# Aixcel_Tiny_STLink_Board_Page1.net
KiCad netlist of a schematic drawn in Altium Designer
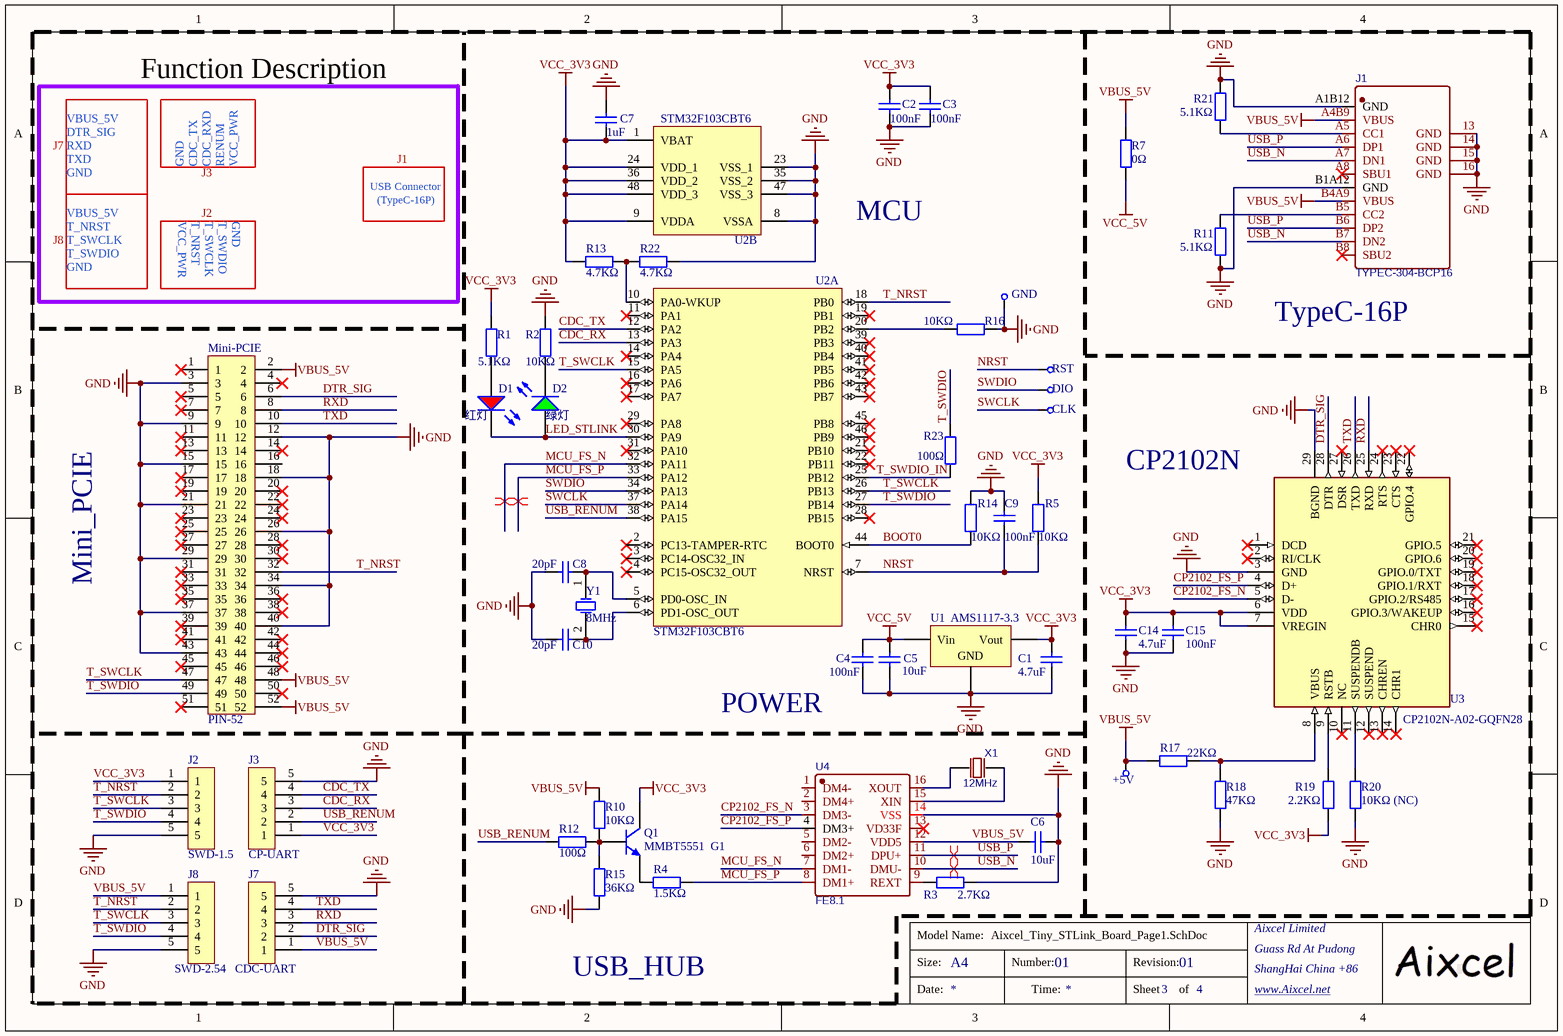
[diagram p0: Aixcel_Tiny_STLink_Board_Page1.SchDoc]

(export (version "E")
  (design (tool "Eeschema 10.0.6"))
  (components
    (comp (ref "+5V")
      (value "CHECK")
      (footprint "CHECK-D")
      (description "测试点")
      (libsource (lib "fszhang") (part "CHECK"))
    )
    (comp (ref "C1")
      (value "4.7uF")
      (footprint "0603_C")
      (description "贴片电容")
      (libsource (lib "Miscellaneous Devices LC") (part "0603 4.7uF (475) 10% 16V"))
    )
    (comp (ref "C2")
      (value "100nF")
      (footprint "0603_C")
      (description "贴片电容")
      (libsource (lib "Miscellaneous Devices LC") (part "0603 100nF (104) 10% 50V"))
    )
    (comp (ref "C3")
      (value "100nF")
      (footprint "0603_C")
      (description "贴片电容")
      (libsource (lib "Miscellaneous Devices LC") (part "0603 100nF (104) 10% 50V"))
    )
    (comp (ref "C4")
      (value "100nF")
      (footprint "0603_C")
      (description "贴片电容")
      (libsource (lib "Miscellaneous Devices LC") (part "0603 100nF (104) 10% 50V"))
    )
    (comp (ref "C5")
      (value "10uF")
      (footprint "0603_C")
      (description "贴片电容")
      (libsource (lib "Miscellaneous Devices LC") (part "0603 10uF (106) 10% 10V"))
    )
    (comp (ref "C6")
      (value "10uF")
      (footprint "0603_C")
      (description "贴片电容")
      (libsource (lib "Miscellaneous Devices LC") (part "0603 10uF (106) 10% 10V"))
    )
    (comp (ref "C7")
      (value "1uF")
      (footprint "0603_C")
      (description "贴片电容")
      (libsource (lib "Miscellaneous Devices LC") (part "0603 1uF (105) 10% 50V"))
    )
    (comp (ref "C8")
      (value "20pF")
      (footprint "0603_C")
      (description "贴片电容")
      (libsource (lib "Miscellaneous Devices LC") (part "0603 20pF (200) 5% 50V"))
    )
    (comp (ref "C9")
      (value "100nF")
      (footprint "0603_C")
      (description "贴片电容")
      (libsource (lib "Miscellaneous Devices LC") (part "0603 100nF (104) 10% 50V"))
    )
    (comp (ref "C10")
      (value "20pF")
      (footprint "0603_C")
      (description "贴片电容")
      (libsource (lib "Miscellaneous Devices LC") (part "0603 20pF (200) 5% 50V"))
    )
    (comp (ref "C14")
      (value "4.7uF")
      (footprint "0603_C")
      (description "贴片电容")
      (libsource (lib "Miscellaneous Devices LC") (part "0603 4.7uF (475) 10% 16V"))
    )
    (comp (ref "C15")
      (value "100nF")
      (footprint "0603_C")
      (description "贴片电容")
      (libsource (lib "Miscellaneous Devices LC") (part "0603 100nF (104) 10% 50V"))
    )
    (comp (ref "CLK")
      (value "CHECK")
      (footprint "CHECK-D")
      (description "测试点")
      (libsource (lib "fszhang") (part "CHECK"))
    )
    (comp (ref "D1")
      (value "红灯")
      (footprint "0603_LED_S1")
      (description "发光二极管")
      (libsource (lib "Miscellaneous Devices LC") (part "0603 红灯"))
    )
    (comp (ref "D2")
      (value "绿灯")
      (footprint "0603_LED_S1")
      (description "发光二极管")
      (libsource (lib "Miscellaneous Devices LC") (part "0603 绿灯"))
    )
    (comp (ref "DIO")
      (value "CHECK")
      (footprint "CHECK-D")
      (description "测试点")
      (libsource (lib "fszhang") (part "CHECK"))
    )
    (comp (ref "GND")
      (value "CHECK")
      (footprint "CHECK-D")
      (description "测试点")
      (libsource (lib "fszhang") (part "CHECK"))
    )
    (comp (ref "J1")
      (value "TYPEC-304-BCP16")
      (footprint "TypeC-16Pin")
      (fields (field (name "BOM_SUPPLIER PART") "C720629") (field (name "CONTRIBUTOR") "LCSC"))
      (libsource (lib "其他") (part "TYPEC-304-BCP16"))
    )
    (comp (ref "J2") (value "SWD-1.5") (footprint "ZH1.5-LI-5P") (libsource (lib "接插件") (part "SIP-5")))
    (comp (ref "J3") (value "CP-UART") (footprint "ZH1.5-LI-5P") (libsource (lib "") (part "SIP-5_1")))
    (comp (ref "J7") (value "CDC-UART") (footprint "2.54XH接插件5P") (libsource (lib "") (part "SIP-5_1")))
    (comp (ref "J8") (value "SWD-2.54") (footprint "2.54XH接插件5P") (libsource (lib "接插件") (part "SIP-5")))
    (comp (ref "Mini-PCIE")
      (value "PIN-52")
      (footprint "PCBComponent_1")
      (libsource (lib "接插件") (part "PIN-52"))
    )
    (comp (ref "Q1")
      (value "MMBT5551  G1")
      (footprint "SOT-23(SOT-23-3)")
      (description "三极管")
      (libsource (lib "Miscellaneous Devices LC") (part "SOT-23 MMBT5551  G1"))
    )
    (comp (ref "R1")
      (value "5.1KΩ")
      (footprint "0603_R")
      (description "贴片电阻")
      (libsource (lib "") (part "0603 5.1KΩ (5101) 1%_1"))
    )
    (comp (ref "R2")
      (value "10KΩ")
      (footprint "0603_R")
      (description "贴片电阻")
      (libsource (lib "") (part "0603 10KΩ (1002) 1%_1"))
    )
    (comp (ref "R3")
      (value "2.7KΩ")
      (footprint "0603_R")
      (description "贴片电阻")
      (libsource (lib "Miscellaneous Devices LC") (part "0603 2.7KΩ (2701) 1%"))
    )
    (comp (ref "R4")
      (value "1.5KΩ")
      (footprint "0603_R")
      (description "贴片电阻")
      (libsource (lib "Miscellaneous Devices LC") (part "0603 1.5KΩ (1501) 1%"))
    )
    (comp (ref "R5")
      (value "10KΩ")
      (footprint "0603_R")
      (description "贴片电阻")
      (libsource (lib "") (part "0603 10KΩ (1002) 1%_1"))
    )
    (comp (ref "R7")
      (value "0Ω")
      (footprint "0805_R")
      (description "贴片电阻")
      (libsource (lib "Miscellaneous Devices LC") (part "0805 0Ω (0R0) 1%"))
    )
    (comp (ref "R10")
      (value "10KΩ")
      (footprint "0603_R")
      (description "贴片电阻")
      (libsource (lib "") (part "0603 10KΩ (1002) 1%_1"))
    )
    (comp (ref "R11")
      (value "5.1KΩ")
      (footprint "0603_R")
      (description "贴片电阻")
      (libsource (lib "Miscellaneous Devices LC") (part "0603 5.1KΩ (5101) 1%"))
    )
    (comp (ref "R12")
      (value "100Ω")
      (footprint "0603_R")
      (description "贴片电阻")
      (libsource (lib "Miscellaneous Devices LC") (part "0603 100Ω (1000) 1%"))
    )
    (comp (ref "R13")
      (value "4.7KΩ")
      (footprint "0603_R")
      (description "贴片电阻")
      (libsource (lib "Miscellaneous Devices LC") (part "0603 4.7KΩ (4701) 1%"))
    )
    (comp (ref "R14")
      (value "10KΩ")
      (footprint "0603_R")
      (description "贴片电阻")
      (libsource (lib "Miscellaneous Devices LC") (part "0603 10KΩ (1002) 1%"))
    )
    (comp (ref "R15")
      (value "36KΩ")
      (footprint "0603_R")
      (description "贴片电阻")
      (libsource (lib "Miscellaneous Devices LC") (part "0603 36KΩ (3602) 1%"))
    )
    (comp (ref "R16")
      (value "10KΩ")
      (footprint "0603_R")
      (description "贴片电阻")
      (libsource (lib "") (part "0603 10KΩ (1002) 1%_2"))
    )
    (comp (ref "R17")
      (value "22KΩ")
      (footprint "0603_R")
      (description "贴片电阻")
      (libsource (lib "Miscellaneous Devices LC") (part "0603 22KΩ (2202) 1%"))
    )
    (comp (ref "R18")
      (value "47KΩ")
      (footprint "0603_R")
      (description "贴片电阻")
      (libsource (lib "Miscellaneous Devices LC") (part "0603 47KΩ (4702) 1%"))
    )
    (comp (ref "R19")
      (value "2.2KΩ")
      (footprint "0603_R")
      (description "贴片电阻")
      (libsource (lib "Miscellaneous Devices LC") (part "0603 2.2KΩ (2201) 1%"))
    )
    (comp (ref "R20")
      (value "10KΩ (NC)")
      (footprint "0603_R")
      (description "贴片电阻")
      (libsource (lib "Miscellaneous Devices LC") (part "0603 10KΩ (1002) 1%"))
    )
    (comp (ref "R21")
      (value "5.1KΩ")
      (footprint "0603_R")
      (description "贴片电阻")
      (libsource (lib "Miscellaneous Devices LC") (part "0603 5.1KΩ (5101) 1%"))
    )
    (comp (ref "R22")
      (value "4.7KΩ")
      (footprint "0603_R")
      (description "贴片电阻")
      (libsource (lib "Miscellaneous Devices LC") (part "0603 4.7KΩ (4701) 1%"))
    )
    (comp (ref "R23")
      (value "100Ω")
      (footprint "0603_R")
      (description "贴片电阻")
      (libsource (lib "") (part "0603 100Ω (1000) 1%_1"))
    )
    (comp (ref "RST")
      (value "CHECK")
      (footprint "CHECK-D")
      (description "测试点")
      (libsource (lib "fszhang") (part "CHECK"))
    )
    (comp (ref "U1")
      (value "AMS1117-3.3")
      (footprint "SOT-223")
      (description "低压差线性稳压(LDO)")
      (libsource (lib "Miscellaneous Devices LC") (part "SOT-223 AMS1117-3.3"))
    )
    (comp (ref "U2")
      (value "STM32F103CBT6")
      (footprint "STM-LQFP48_L")
      (libsource (lib "STMicroelectronics STM32 F1") (part "STM32F103CBT6"))
    )
    (comp (ref "U3")
      (value "CP2102N-A02-GQFN28")
      (footprint "SamacSys:QFN50P500X500X80-29N-D")
      (description "Integrated Circuit")
      (fields (field (name "MOUSER2 PART NUMBER") "634-CP2102NA02GQFN28"))
      (libsource (lib "*") (part "CP2102N-A02-GQFN28"))
    )
    (comp (ref "U4")
      (value "FE8.1")
      (footprint "SSOP-16_L4.9-W3.9-P0.64-LS6.0-BL")
      (fields (field (name "CONTRIBUTOR") "私有工程"))
      (libsource (lib "FE8.1") (part "FE8.1"))
    )
    (comp (ref "X1")
      (value "12MHz")
      (footprint "12MHz")
      (fields
        (field (name "BOM_SUPPLIER PART") "C33728")
        (field (name "BOM_MANUFACTURER PART") "X503212MSD2GC")
      )
      (libsource (lib "其他") (part "12MHz"))
    )
    (comp (ref "Y1")
      (value "8MHz")
      (footprint "SMD-5032_2P")
      (description "贴片晶振")
      (libsource (lib "Miscellaneous Devices LC") (part "SMD-5032_2P 8MHz 20ppm 20pF"))
    )
  )
  (nets
    (net (code "1") (name "/BOOT0") (class "Default")
      (node (ref "R14") (pin "2") (pinfunction "2_2") (pintype "passive"))
      (node (ref "U2") (pin "44") (pinfunction "BOOT0_44") (pintype "input"))
    )
    (net (code "2") (name "/CDC_RX") (class "Default")
      (node (ref "J3") (pin "3") (pinfunction "3_3") (pintype "passive"))
      (node (ref "U2") (pin "13") (pinfunction "PA3_13") (pintype "bidirectional"))
    )
    (net (code "3") (name "/CDC_TX") (class "Default")
      (node (ref "J3") (pin "4") (pinfunction "4_4") (pintype "passive"))
      (node (ref "U2") (pin "12") (pinfunction "PA2_12") (pintype "bidirectional"))
    )
    (net (code "4") (name "/CP2102_FS_N") (class "Default")
      (node (ref "U3") (pin "5") (pinfunction "D-_5") (pintype "bidirectional"))
      (node (ref "U4") (pin "3") (pinfunction "DM3-_3") (pintype "passive"))
    )
    (net (code "5") (name "/CP2102_FS_P") (class "Default")
      (node (ref "U3") (pin "4") (pinfunction "D+_4") (pintype "bidirectional"))
      (node (ref "U4") (pin "4") (pinfunction "DM3+_4") (pintype "passive"))
    )
    (net (code "6") (name "/DTR_SIG") (class "Default")
      (node (ref "J7") (pin "2") (pinfunction "2_2") (pintype "passive"))
      (node (ref "Mini-PCIE") (pin "6") (pinfunction "6_6") (pintype "passive"))
      (node (ref "U3") (pin "28") (pinfunction "DTR_28") (pintype "output"))
    )
    (net (code "7") (name "/LED_STLINK") (class "Default")
      (node (ref "D1") (pin "K") (pinfunction "K_K") (pintype "passive"))
      (node (ref "D2") (pin "A") (pinfunction "A_A") (pintype "passive"))
      (node (ref "U2") (pin "30") (pinfunction "PA9_30") (pintype "bidirectional"))
    )
    (net (code "8") (name "/MCU_FS_N") (class "Default")
      (node (ref "U2") (pin "32") (pinfunction "PA11_32") (pintype "bidirectional"))
      (node (ref "U4") (pin "7") (pinfunction "DM1-_7") (pintype "passive"))
    )
    (net (code "9") (name "/MCU_FS_P") (class "Default")
      (node (ref "R4") (pin "1") (pinfunction "1_1") (pintype "passive"))
      (node (ref "U2") (pin "33") (pinfunction "PA12_33") (pintype "bidirectional"))
      (node (ref "U4") (pin "8") (pinfunction "DM1+_8") (pintype "passive"))
    )
    (net (code "10") (name "/NRST") (class "Default")
      (node (ref "C9") (pin "1") (pinfunction "1_1") (pintype "passive"))
      (node (ref "R5") (pin "1") (pinfunction "1_1") (pintype "passive"))
      (node (ref "RST") (pin "1") (pinfunction "1_1") (pintype "passive"))
      (node (ref "U2") (pin "7") (pinfunction "NRST_7") (pintype "bidirectional"))
    )
    (net (code "11") (name "/RXD") (class "Default")
      (node (ref "J7") (pin "3") (pinfunction "3_3") (pintype "passive"))
      (node (ref "Mini-PCIE") (pin "8") (pinfunction "8_8") (pintype "passive"))
      (node (ref "U3") (pin "25") (pinfunction "RXD_25") (pintype "input"))
    )
    (net (code "12") (name "/SWCLK") (class "Default")
      (node (ref "CLK") (pin "1") (pinfunction "1_1") (pintype "passive"))
      (node (ref "U2") (pin "37") (pinfunction "PA14_37") (pintype "bidirectional"))
    )
    (net (code "13") (name "/SWDIO") (class "Default")
      (node (ref "DIO") (pin "1") (pinfunction "1_1") (pintype "passive"))
      (node (ref "U2") (pin "34") (pinfunction "PA13_34") (pintype "bidirectional"))
    )
    (net (code "14") (name "/TXD") (class "Default")
      (node (ref "J7") (pin "4") (pinfunction "4_4") (pintype "passive"))
      (node (ref "Mini-PCIE") (pin "10") (pinfunction "10_10") (pintype "passive"))
      (node (ref "U3") (pin "26") (pinfunction "TXD_26") (pintype "output"))
    )
    (net (code "15") (name "/T_NRST") (class "Default")
      (node (ref "J2") (pin "2") (pinfunction "2_2") (pintype "passive"))
      (node (ref "J8") (pin "2") (pinfunction "2_2") (pintype "passive"))
      (node (ref "Mini-PCIE") (pin "32") (pinfunction "32_32") (pintype "passive"))
      (node (ref "U2") (pin "18") (pinfunction "PB0_18") (pintype "bidirectional"))
    )
    (net (code "16") (name "/T_SWCLK") (class "Default")
      (node (ref "J2") (pin "3") (pinfunction "3_3") (pintype "passive"))
      (node (ref "J8") (pin "3") (pinfunction "3_3") (pintype "passive"))
      (node (ref "Mini-PCIE") (pin "47") (pinfunction "47_47") (pintype "passive"))
      (node (ref "U2") (pin "15") (pinfunction "PA5_15") (pintype "bidirectional"))
      (node (ref "U2") (pin "26") (pinfunction "PB13_26") (pintype "bidirectional"))
    )
    (net (code "17") (name "/T_SWDIO") (class "Default")
      (node (ref "J2") (pin "4") (pinfunction "4_4") (pintype "passive"))
      (node (ref "J8") (pin "4") (pinfunction "4_4") (pintype "passive"))
      (node (ref "Mini-PCIE") (pin "49") (pinfunction "49_49") (pintype "passive"))
      (node (ref "R23") (pin "2") (pinfunction "2_2") (pintype "passive"))
      (node (ref "U2") (pin "27") (pinfunction "PB14_27") (pintype "bidirectional"))
    )
    (net (code "18") (name "/T_SWDIO_IN") (class "Default")
      (node (ref "R23") (pin "1") (pinfunction "1_1") (pintype "passive"))
      (node (ref "U2") (pin "25") (pinfunction "PB12_25") (pintype "bidirectional"))
    )
    (net (code "19") (name "/USB_N") (class "Default")
      (node (ref "J1") (pin "A7") (pinfunction "DN1_A7") (pintype "passive"))
      (node (ref "J1") (pin "B7") (pinfunction "DN2_B7") (pintype "passive"))
      (node (ref "U4") (pin "10") (pinfunction "DMU-_10") (pintype "passive"))
    )
    (net (code "20") (name "/USB_P") (class "Default")
      (node (ref "J1") (pin "A6") (pinfunction "DP1_A6") (pintype "passive"))
      (node (ref "J1") (pin "B6") (pinfunction "DP2_B6") (pintype "passive"))
      (node (ref "U4") (pin "11") (pinfunction "DPU+_11") (pintype "passive"))
    )
    (net (code "21") (name "/USB_RENUM") (class "Default")
      (node (ref "J3") (pin "2") (pinfunction "2_2") (pintype "passive"))
      (node (ref "R12") (pin "1") (pinfunction "1_1") (pintype "passive"))
      (node (ref "U2") (pin "38") (pinfunction "PA15_38") (pintype "bidirectional"))
    )
    (net (code "22") (name "GND") (class "Default")
      (node (ref "C1") (pin "1") (pinfunction "1_1") (pintype "passive"))
      (node (ref "C10") (pin "1") (pinfunction "1_1") (pintype "passive"))
      (node (ref "C14") (pin "1") (pinfunction "1_1") (pintype "passive"))
      (node (ref "C15") (pin "1") (pinfunction "1_1") (pintype "passive"))
      (node (ref "C2") (pin "2") (pinfunction "2_2") (pintype "passive"))
      (node (ref "C3") (pin "2") (pinfunction "2_2") (pintype "passive"))
      (node (ref "C4") (pin "1") (pinfunction "1_1") (pintype "passive"))
      (node (ref "C5") (pin "1") (pinfunction "1_1") (pintype "passive"))
      (node (ref "C6") (pin "1") (pinfunction "1_1") (pintype "passive"))
      (node (ref "C7") (pin "2") (pinfunction "2_2") (pintype "passive"))
      (node (ref "C8") (pin "1") (pinfunction "1_1") (pintype "passive"))
      (node (ref "C9") (pin "2") (pinfunction "2_2") (pintype "passive"))
      (node (ref "GND") (pin "1") (pinfunction "1_1") (pintype "passive"))
      (node (ref "J1") (pin "13") (pinfunction "GND_13") (pintype "passive"))
      (node (ref "J1") (pin "14") (pinfunction "GND_14") (pintype "passive"))
      (node (ref "J1") (pin "15") (pinfunction "GND_15") (pintype "passive"))
      (node (ref "J1") (pin "16") (pinfunction "GND_16") (pintype "passive"))
      (node (ref "J1") (pin "A1B12") (pinfunction "GND_A1B12") (pintype "passive"))
      (node (ref "J1") (pin "B1A12") (pinfunction "GND_B1A12") (pintype "passive"))
      (node (ref "J2") (pin "5") (pinfunction "5_5") (pintype "passive"))
      (node (ref "J3") (pin "5") (pinfunction "5_5") (pintype "passive"))
      (node (ref "J7") (pin "5") (pinfunction "5_5") (pintype "passive"))
      (node (ref "J8") (pin "5") (pinfunction "5_5") (pintype "passive"))
      (node (ref "Mini-PCIE") (pin "12") (pinfunction "12_12") (pintype "passive"))
      (node (ref "Mini-PCIE") (pin "15") (pinfunction "15_15") (pintype "passive"))
      (node (ref "Mini-PCIE") (pin "18") (pinfunction "18_18") (pintype "passive"))
      (node (ref "Mini-PCIE") (pin "21") (pinfunction "21_21") (pintype "passive"))
      (node (ref "Mini-PCIE") (pin "26") (pinfunction "26_26") (pintype "passive"))
      (node (ref "Mini-PCIE") (pin "29") (pinfunction "29_29") (pintype "passive"))
      (node (ref "Mini-PCIE") (pin "3") (pinfunction "3_3") (pintype "passive"))
      (node (ref "Mini-PCIE") (pin "34") (pinfunction "34_34") (pintype "passive"))
      (node (ref "Mini-PCIE") (pin "37") (pinfunction "37_37") (pintype "passive"))
      (node (ref "Mini-PCIE") (pin "40") (pinfunction "40_40") (pintype "passive"))
      (node (ref "Mini-PCIE") (pin "43") (pinfunction "43_43") (pintype "passive"))
      (node (ref "Mini-PCIE") (pin "9") (pinfunction "9_9") (pintype "passive"))
      (node (ref "R11") (pin "1") (pinfunction "1_1") (pintype "passive"))
      (node (ref "R14") (pin "1") (pinfunction "1_1") (pintype "passive"))
      (node (ref "R15") (pin "1") (pinfunction "1_1") (pintype "passive"))
      (node (ref "R16") (pin "1") (pinfunction "1_1") (pintype "passive"))
      (node (ref "R18") (pin "1") (pinfunction "1_1") (pintype "passive"))
      (node (ref "R2") (pin "2") (pinfunction "2_2") (pintype "passive"))
      (node (ref "R20") (pin "2") (pinfunction "2_2") (pintype "passive"))
      (node (ref "R21") (pin "2") (pinfunction "2_2") (pintype "passive"))
      (node (ref "R22") (pin "1") (pinfunction "1_1") (pintype "passive"))
      (node (ref "R3") (pin "2") (pinfunction "2_2") (pintype "passive"))
      (node (ref "U1") (pin "1") (pinfunction "GND_1") (pintype "passive"))
      (node (ref "U2") (pin "23") (pinfunction "VSS_1_23") (pintype "power_in"))
      (node (ref "U2") (pin "35") (pinfunction "VSS_2_35") (pintype "power_in"))
      (node (ref "U2") (pin "47") (pinfunction "VSS_3_47") (pintype "power_in"))
      (node (ref "U2") (pin "8") (pinfunction "VSSA_8") (pintype "power_in"))
      (node (ref "U3") (pin "29") (pinfunction "BGND_29") (pintype "power_in"))
      (node (ref "U3") (pin "3") (pinfunction "GND_3") (pintype "power_in"))
      (node (ref "U4") (pin "14") (pinfunction "VSS_14") (pintype "passive"))
    )
    (net (code "23") (name "Net-(D1-PadA)") (class "Default")
      (node (ref "D1") (pin "A") (pinfunction "A_A") (pintype "passive"))
      (node (ref "R1") (pin "2") (pinfunction "2_2") (pintype "passive"))
    )
    (net (code "24") (name "Net-(D2-PadK)") (class "Default")
      (node (ref "D2") (pin "K") (pinfunction "K_K") (pintype "passive"))
      (node (ref "R2") (pin "1") (pinfunction "1_1") (pintype "passive"))
    )
    (net (code "25") (name "Net-(J1-CC1)") (class "Default")
      (node (ref "J1") (pin "A5") (pinfunction "CC1_A5") (pintype "passive"))
      (node (ref "R21") (pin "1") (pinfunction "1_1") (pintype "passive"))
    )
    (net (code "26") (name "Net-(J1-CC2)") (class "Default")
      (node (ref "J1") (pin "B5") (pinfunction "CC2_B5") (pintype "passive"))
      (node (ref "R11") (pin "2") (pinfunction "2_2") (pintype "passive"))
    )
    (net (code "27") (name "Net-(Q1-B)") (class "Default")
      (node (ref "Q1") (pin "1") (pinfunction "B_1") (pintype "passive"))
      (node (ref "R10") (pin "1") (pinfunction "1_1") (pintype "passive"))
      (node (ref "R12") (pin "2") (pinfunction "2_2") (pintype "passive"))
      (node (ref "R15") (pin "2") (pinfunction "2_2") (pintype "passive"))
    )
    (net (code "28") (name "Net-(Q1-E)") (class "Default")
      (node (ref "Q1") (pin "2") (pinfunction "E_2") (pintype "passive"))
      (node (ref "R4") (pin "2") (pinfunction "2_2") (pintype "passive"))
    )
    (net (code "29") (name "Net-(U2A-PA0-WKUP)") (class "Default")
      (node (ref "R13") (pin "1") (pinfunction "1_1") (pintype "passive"))
      (node (ref "R22") (pin "2") (pinfunction "2_2") (pintype "passive"))
      (node (ref "U2") (pin "10") (pinfunction "PA0-WKUP_10") (pintype "bidirectional"))
    )
    (net (code "30") (name "Net-(U2A-PB2)") (class "Default")
      (node (ref "R16") (pin "2") (pinfunction "2_2") (pintype "passive"))
      (node (ref "U2") (pin "20") (pinfunction "PB2_20") (pintype "bidirectional"))
    )
    (net (code "31") (name "Net-(U2A-PD0-OSC_IN)") (class "Default")
      (node (ref "C8") (pin "2") (pinfunction "2_2") (pintype "passive"))
      (node (ref "U2") (pin "5") (pinfunction "PD0-OSC_IN_5") (pintype "bidirectional"))
      (node (ref "Y1") (pin "1") (pinfunction "OSC1_1") (pintype "passive"))
    )
    (net (code "32") (name "Net-(U2A-PD1-OSC_OUT)") (class "Default")
      (node (ref "C10") (pin "2") (pinfunction "2_2") (pintype "passive"))
      (node (ref "U2") (pin "6") (pinfunction "PD1-OSC_OUT_6") (pintype "bidirectional"))
      (node (ref "Y1") (pin "2") (pinfunction "OSC2_2") (pintype "passive"))
    )
    (net (code "33") (name "Net-(U3-RSTB)") (class "Default")
      (node (ref "R19") (pin "2") (pinfunction "2_2") (pintype "passive"))
      (node (ref "U3") (pin "9") (pinfunction "RSTB_9") (pintype "input"))
    )
    (net (code "34") (name "Net-(U3-SUSPENDB)") (class "Default")
      (node (ref "R20") (pin "1") (pinfunction "1_1") (pintype "passive"))
      (node (ref "U3") (pin "11") (pinfunction "SUSPENDB_11") (pintype "output"))
    )
    (net (code "35") (name "Net-(U3-VBUS)") (class "Default")
      (node (ref "R17") (pin "2") (pinfunction "2_2") (pintype "passive"))
      (node (ref "R18") (pin "2") (pinfunction "2_2") (pintype "passive"))
      (node (ref "U3") (pin "8") (pinfunction "VBUS_8") (pintype "input"))
    )
    (net (code "36") (name "Net-(U4-REXT)") (class "Default")
      (node (ref "R3") (pin "1") (pinfunction "1_1") (pintype "passive"))
      (node (ref "U4") (pin "9") (pinfunction "REXT_9") (pintype "passive"))
    )
    (net (code "37") (name "Net-(U4-XIN)") (class "Default")
      (node (ref "U4") (pin "15") (pinfunction "XIN_15") (pintype "passive"))
      (node (ref "X1") (pin "2") (pinfunction "OSC2_2") (pintype "passive"))
    )
    (net (code "38") (name "Net-(U4-XOUT)") (class "Default")
      (node (ref "U4") (pin "16") (pinfunction "XOUT_16") (pintype "passive"))
      (node (ref "X1") (pin "1") (pinfunction "OSC1_1") (pintype "passive"))
    )
    (net (code "39") (name "VBUS_5V") (class "Default")
      (node (ref "+5V") (pin "1") (pinfunction "1_1") (pintype "passive"))
      (node (ref "C6") (pin "2") (pinfunction "2_2") (pintype "passive"))
      (node (ref "J1") (pin "A4B9") (pinfunction "VBUS_A4B9") (pintype "passive"))
      (node (ref "J1") (pin "B4A9") (pinfunction "VBUS_B4A9") (pintype "passive"))
      (node (ref "J7") (pin "1") (pinfunction "1_1") (pintype "passive"))
      (node (ref "J8") (pin "1") (pinfunction "1_1") (pintype "passive"))
      (node (ref "Mini-PCIE") (pin "2") (pinfunction "2_2") (pintype "passive"))
      (node (ref "Mini-PCIE") (pin "48") (pinfunction "48_48") (pintype "passive"))
      (node (ref "Mini-PCIE") (pin "52") (pinfunction "52_52") (pintype "passive"))
      (node (ref "R10") (pin "2") (pinfunction "2_2") (pintype "passive"))
      (node (ref "R17") (pin "1") (pinfunction "1_1") (pintype "passive"))
      (node (ref "R7") (pin "2") (pinfunction "2_2") (pintype "passive"))
      (node (ref "U4") (pin "12") (pinfunction "VDD5_12") (pintype "passive"))
    )
    (net (code "40") (name "VCC_3V3") (class "Default")
      (node (ref "C1") (pin "2") (pinfunction "2_2") (pintype "passive"))
      (node (ref "C14") (pin "2") (pinfunction "2_2") (pintype "passive"))
      (node (ref "C15") (pin "2") (pinfunction "2_2") (pintype "passive"))
      (node (ref "C2") (pin "1") (pinfunction "1_1") (pintype "passive"))
      (node (ref "C3") (pin "1") (pinfunction "1_1") (pintype "passive"))
      (node (ref "C7") (pin "1") (pinfunction "1_1") (pintype "passive"))
      (node (ref "J2") (pin "1") (pinfunction "1_1") (pintype "passive"))
      (node (ref "J3") (pin "1") (pinfunction "1_1") (pintype "passive"))
      (node (ref "Q1") (pin "3") (pinfunction "C_3") (pintype "passive"))
      (node (ref "R1") (pin "1") (pinfunction "1_1") (pintype "passive"))
      (node (ref "R13") (pin "2") (pinfunction "2_2") (pintype "passive"))
      (node (ref "R19") (pin "1") (pinfunction "1_1") (pintype "passive"))
      (node (ref "R5") (pin "2") (pinfunction "2_2") (pintype "passive"))
      (node (ref "U1") (pin "2") (pinfunction "Vout_2") (pintype "passive"))
      (node (ref "U2") (pin "1") (pinfunction "VBAT_1") (pintype "power_in"))
      (node (ref "U2") (pin "24") (pinfunction "VDD_1_24") (pintype "power_in"))
      (node (ref "U2") (pin "36") (pinfunction "VDD_2_36") (pintype "power_in"))
      (node (ref "U2") (pin "48") (pinfunction "VDD_3_48") (pintype "power_in"))
      (node (ref "U2") (pin "9") (pinfunction "VDDA_9") (pintype "power_in"))
      (node (ref "U3") (pin "6") (pinfunction "VDD_6") (pintype "power_in"))
      (node (ref "U3") (pin "7") (pinfunction "VREGIN_7") (pintype "power_in"))
    )
    (net (code "41") (name "VCC_5V") (class "Default")
      (node (ref "C4") (pin "2") (pinfunction "2_2") (pintype "passive"))
      (node (ref "C5") (pin "2") (pinfunction "2_2") (pintype "passive"))
      (node (ref "R7") (pin "1") (pinfunction "1_1") (pintype "passive"))
      (node (ref "U1") (pin "3") (pinfunction "Vin_3") (pintype "passive"))
    )
    (net (code "42") (name "unconnected-(J1-SBU1-PadA8)") (class "Default")
      (node (ref "J1") (pin "A8") (pinfunction "SBU1_A8") (pintype "passive+no_connect"))
    )
    (net (code "43") (name "unconnected-(J1-SBU2-PadB8)") (class "Default")
      (node (ref "J1") (pin "B8") (pinfunction "SBU2_B8") (pintype "passive+no_connect"))
    )
    (net (code "44") (name "unconnected-(Mini-PCIE-Pad1)") (class "Default")
      (node (ref "Mini-PCIE") (pin "1") (pinfunction "1_1") (pintype "passive+no_connect"))
    )
    (net (code "45") (name "unconnected-(Mini-PCIE-Pad4)") (class "Default")
      (node (ref "Mini-PCIE") (pin "4") (pinfunction "4_4") (pintype "passive+no_connect"))
    )
    (net (code "46") (name "unconnected-(Mini-PCIE-Pad5)") (class "Default")
      (node (ref "Mini-PCIE") (pin "5") (pinfunction "5_5") (pintype "passive+no_connect"))
    )
    (net (code "47") (name "unconnected-(Mini-PCIE-Pad7)") (class "Default")
      (node (ref "Mini-PCIE") (pin "7") (pinfunction "7_7") (pintype "passive+no_connect"))
    )
    (net (code "48") (name "unconnected-(Mini-PCIE-Pad11)") (class "Default")
      (node (ref "Mini-PCIE") (pin "11") (pinfunction "11_11") (pintype "passive+no_connect"))
    )
    (net (code "49") (name "unconnected-(Mini-PCIE-Pad13)") (class "Default")
      (node (ref "Mini-PCIE") (pin "13") (pinfunction "13_13") (pintype "passive+no_connect"))
    )
    (net (code "50") (name "unconnected-(Mini-PCIE-Pad14)") (class "Default")
      (node (ref "Mini-PCIE") (pin "14") (pinfunction "14_14") (pintype "passive+no_connect"))
    )
    (net (code "51") (name "unconnected-(Mini-PCIE-Pad16)") (class "Default")
      (node (ref "Mini-PCIE") (pin "16") (pinfunction "16_16") (pintype "passive"))
    )
    (net (code "52") (name "unconnected-(Mini-PCIE-Pad17)") (class "Default")
      (node (ref "Mini-PCIE") (pin "17") (pinfunction "17_17") (pintype "passive+no_connect"))
    )
    (net (code "53") (name "unconnected-(Mini-PCIE-Pad19)") (class "Default")
      (node (ref "Mini-PCIE") (pin "19") (pinfunction "19_19") (pintype "passive+no_connect"))
    )
    (net (code "54") (name "unconnected-(Mini-PCIE-Pad20)") (class "Default")
      (node (ref "Mini-PCIE") (pin "20") (pinfunction "20_20") (pintype "passive+no_connect"))
    )
    (net (code "55") (name "unconnected-(Mini-PCIE-Pad22)") (class "Default")
      (node (ref "Mini-PCIE") (pin "22") (pinfunction "22_22") (pintype "passive+no_connect"))
    )
    (net (code "56") (name "unconnected-(Mini-PCIE-Pad23)") (class "Default")
      (node (ref "Mini-PCIE") (pin "23") (pinfunction "23_23") (pintype "passive+no_connect"))
    )
    (net (code "57") (name "unconnected-(Mini-PCIE-Pad24)") (class "Default")
      (node (ref "Mini-PCIE") (pin "24") (pinfunction "24_24") (pintype "passive+no_connect"))
    )
    (net (code "58") (name "unconnected-(Mini-PCIE-Pad25)") (class "Default")
      (node (ref "Mini-PCIE") (pin "25") (pinfunction "25_25") (pintype "passive+no_connect"))
    )
    (net (code "59") (name "unconnected-(Mini-PCIE-Pad27)") (class "Default")
      (node (ref "Mini-PCIE") (pin "27") (pinfunction "27_27") (pintype "passive+no_connect"))
    )
    (net (code "60") (name "unconnected-(Mini-PCIE-Pad28)") (class "Default")
      (node (ref "Mini-PCIE") (pin "28") (pinfunction "28_28") (pintype "passive+no_connect"))
    )
    (net (code "61") (name "unconnected-(Mini-PCIE-Pad30)") (class "Default")
      (node (ref "Mini-PCIE") (pin "30") (pinfunction "30_30") (pintype "passive+no_connect"))
    )
    (net (code "62") (name "unconnected-(Mini-PCIE-Pad31)") (class "Default")
      (node (ref "Mini-PCIE") (pin "31") (pinfunction "31_31") (pintype "passive+no_connect"))
    )
    (net (code "63") (name "unconnected-(Mini-PCIE-Pad33)") (class "Default")
      (node (ref "Mini-PCIE") (pin "33") (pinfunction "33_33") (pintype "passive+no_connect"))
    )
    (net (code "64") (name "unconnected-(Mini-PCIE-Pad35)") (class "Default")
      (node (ref "Mini-PCIE") (pin "35") (pinfunction "35_35") (pintype "passive+no_connect"))
    )
    (net (code "65") (name "unconnected-(Mini-PCIE-Pad36)") (class "Default")
      (node (ref "Mini-PCIE") (pin "36") (pinfunction "36_36") (pintype "passive+no_connect"))
    )
    (net (code "66") (name "unconnected-(Mini-PCIE-Pad38)") (class "Default")
      (node (ref "Mini-PCIE") (pin "38") (pinfunction "38_38") (pintype "passive+no_connect"))
    )
    (net (code "67") (name "unconnected-(Mini-PCIE-Pad39)") (class "Default")
      (node (ref "Mini-PCIE") (pin "39") (pinfunction "39_39") (pintype "passive+no_connect"))
    )
    (net (code "68") (name "unconnected-(Mini-PCIE-Pad41)") (class "Default")
      (node (ref "Mini-PCIE") (pin "41") (pinfunction "41_41") (pintype "passive+no_connect"))
    )
    (net (code "69") (name "unconnected-(Mini-PCIE-Pad42)") (class "Default")
      (node (ref "Mini-PCIE") (pin "42") (pinfunction "42_42") (pintype "passive+no_connect"))
    )
    (net (code "70") (name "unconnected-(Mini-PCIE-Pad44)") (class "Default")
      (node (ref "Mini-PCIE") (pin "44") (pinfunction "44_44") (pintype "passive+no_connect"))
    )
    (net (code "71") (name "unconnected-(Mini-PCIE-Pad45)") (class "Default")
      (node (ref "Mini-PCIE") (pin "45") (pinfunction "45_45") (pintype "passive+no_connect"))
    )
    (net (code "72") (name "unconnected-(Mini-PCIE-Pad46)") (class "Default")
      (node (ref "Mini-PCIE") (pin "46") (pinfunction "46_46") (pintype "passive+no_connect"))
    )
    (net (code "73") (name "unconnected-(Mini-PCIE-Pad50)") (class "Default")
      (node (ref "Mini-PCIE") (pin "50") (pinfunction "50_50") (pintype "passive+no_connect"))
    )
    (net (code "74") (name "unconnected-(Mini-PCIE-Pad51)") (class "Default")
      (node (ref "Mini-PCIE") (pin "51") (pinfunction "51_51") (pintype "passive+no_connect"))
    )
    (net (code "75") (name "unconnected-(U2A-PA1-Pad11)") (class "Default")
      (node (ref "U2") (pin "11") (pinfunction "PA1_11") (pintype "bidirectional+no_connect"))
    )
    (net (code "76") (name "unconnected-(U2A-PA4-Pad14)") (class "Default")
      (node (ref "U2") (pin "14") (pinfunction "PA4_14") (pintype "bidirectional+no_connect"))
    )
    (net (code "77") (name "unconnected-(U2A-PA6-Pad16)") (class "Default")
      (node (ref "U2") (pin "16") (pinfunction "PA6_16") (pintype "bidirectional+no_connect"))
    )
    (net (code "78") (name "unconnected-(U2A-PA7-Pad17)") (class "Default")
      (node (ref "U2") (pin "17") (pinfunction "PA7_17") (pintype "bidirectional+no_connect"))
    )
    (net (code "79") (name "unconnected-(U2A-PA8-Pad29)") (class "Default")
      (node (ref "U2") (pin "29") (pinfunction "PA8_29") (pintype "bidirectional+no_connect"))
    )
    (net (code "80") (name "unconnected-(U2A-PA10-Pad31)") (class "Default")
      (node (ref "U2") (pin "31") (pinfunction "PA10_31") (pintype "bidirectional+no_connect"))
    )
    (net (code "81") (name "unconnected-(U2A-PB1-Pad19)") (class "Default")
      (node (ref "U2") (pin "19") (pinfunction "PB1_19") (pintype "bidirectional+no_connect"))
    )
    (net (code "82") (name "unconnected-(U2A-PB3-Pad39)") (class "Default")
      (node (ref "U2") (pin "39") (pinfunction "PB3_39") (pintype "bidirectional+no_connect"))
    )
    (net (code "83") (name "unconnected-(U2A-PB4-Pad40)") (class "Default")
      (node (ref "U2") (pin "40") (pinfunction "PB4_40") (pintype "bidirectional+no_connect"))
    )
    (net (code "84") (name "unconnected-(U2A-PB5-Pad41)") (class "Default")
      (node (ref "U2") (pin "41") (pinfunction "PB5_41") (pintype "bidirectional+no_connect"))
    )
    (net (code "85") (name "unconnected-(U2A-PB6-Pad42)") (class "Default")
      (node (ref "U2") (pin "42") (pinfunction "PB6_42") (pintype "bidirectional+no_connect"))
    )
    (net (code "86") (name "unconnected-(U2A-PB7-Pad43)") (class "Default")
      (node (ref "U2") (pin "43") (pinfunction "PB7_43") (pintype "bidirectional+no_connect"))
    )
    (net (code "87") (name "unconnected-(U2A-PB8-Pad45)") (class "Default")
      (node (ref "U2") (pin "45") (pinfunction "PB8_45") (pintype "bidirectional+no_connect"))
    )
    (net (code "88") (name "unconnected-(U2A-PB9-Pad46)") (class "Default")
      (node (ref "U2") (pin "46") (pinfunction "PB9_46") (pintype "bidirectional+no_connect"))
    )
    (net (code "89") (name "unconnected-(U2A-PB10-Pad21)") (class "Default")
      (node (ref "U2") (pin "21") (pinfunction "PB10_21") (pintype "bidirectional+no_connect"))
    )
    (net (code "90") (name "unconnected-(U2A-PB11-Pad22)") (class "Default")
      (node (ref "U2") (pin "22") (pinfunction "PB11_22") (pintype "bidirectional+no_connect"))
    )
    (net (code "91") (name "unconnected-(U2A-PB15-Pad28)") (class "Default")
      (node (ref "U2") (pin "28") (pinfunction "PB15_28") (pintype "bidirectional+no_connect"))
    )
    (net (code "92") (name "unconnected-(U2A-PC13-TAMPER-RTC-Pad2)") (class "Default")
      (node (ref "U2") (pin "2") (pinfunction "PC13-TAMPER-RTC_2") (pintype "bidirectional+no_connect"))
    )
    (net (code "93") (name "unconnected-(U2A-PC14-OSC32_IN-Pad3)") (class "Default")
      (node (ref "U2") (pin "3") (pinfunction "PC14-OSC32_IN_3") (pintype "bidirectional+no_connect"))
    )
    (net (code "94") (name "unconnected-(U2A-PC15-OSC32_OUT-Pad4)") (class "Default")
      (node (ref "U2") (pin "4") (pinfunction "PC15-OSC32_OUT_4") (pintype "bidirectional+no_connect"))
    )
    (net (code "95") (name "unconnected-(U3-CHR0-Pad15)") (class "Default")
      (node (ref "U3") (pin "15") (pinfunction "CHR0_15") (pintype "output+no_connect"))
    )
    (net (code "96") (name "unconnected-(U3-CHR1-Pad14)") (class "Default")
      (node (ref "U3") (pin "14") (pinfunction "CHR1_14") (pintype "output+no_connect"))
    )
    (net (code "97") (name "unconnected-(U3-CHREN-Pad13)") (class "Default")
      (node (ref "U3") (pin "13") (pinfunction "CHREN_13") (pintype "output+no_connect"))
    )
    (net (code "98") (name "unconnected-(U3-CTS-Pad23)") (class "Default")
      (node (ref "U3") (pin "23") (pinfunction "CTS_23") (pintype "input+no_connect"))
    )
    (net (code "99") (name "unconnected-(U3-DCD-Pad1)") (class "Default")
      (node (ref "U3") (pin "1") (pinfunction "DCD_1") (pintype "input+no_connect"))
    )
    (net (code "100") (name "unconnected-(U3-DSR-Pad27)") (class "Default")
      (node (ref "U3") (pin "27") (pinfunction "DSR_27") (pintype "input+no_connect"))
    )
    (net (code "101") (name "unconnected-(U3-GPIO.0{slash}TXT-Pad19)") (class "Default")
      (node (ref "U3") (pin "19") (pinfunction "GPIO.0/TXT_19") (pintype "bidirectional+no_connect"))
    )
    (net (code "102") (name "unconnected-(U3-GPIO.1{slash}RXT-Pad18)") (class "Default")
      (node (ref "U3") (pin "18") (pinfunction "GPIO.1/RXT_18") (pintype "bidirectional+no_connect"))
    )
    (net (code "103") (name "unconnected-(U3-GPIO.2{slash}RS485-Pad17)") (class "Default")
      (node (ref "U3") (pin "17") (pinfunction "GPIO.2/RS485_17") (pintype "bidirectional+no_connect"))
    )
    (net (code "104") (name "unconnected-(U3-GPIO.3{slash}WAKEUP-Pad16)") (class "Default")
      (node (ref "U3") (pin "16") (pinfunction "GPIO.3/WAKEUP_16") (pintype "bidirectional+no_connect"))
    )
    (net (code "105") (name "unconnected-(U3-GPIO.4-Pad22)") (class "Default")
      (node (ref "U3") (pin "22") (pinfunction "GPIO.4_22") (pintype "bidirectional+no_connect"))
    )
    (net (code "106") (name "unconnected-(U3-GPIO.5-Pad21)") (class "Default")
      (node (ref "U3") (pin "21") (pinfunction "GPIO.5_21") (pintype "bidirectional+no_connect"))
    )
    (net (code "107") (name "unconnected-(U3-GPIO.6-Pad20)") (class "Default")
      (node (ref "U3") (pin "20") (pinfunction "GPIO.6_20") (pintype "bidirectional+no_connect"))
    )
    (net (code "108") (name "unconnected-(U3-NC-Pad10)") (class "Default")
      (node (ref "U3") (pin "10") (pinfunction "NC_10") (pintype "passive+no_connect"))
    )
    (net (code "109") (name "unconnected-(U3-RI{slash}CLK-Pad2)") (class "Default")
      (node (ref "U3") (pin "2") (pinfunction "RI/CLK_2") (pintype "bidirectional+no_connect"))
    )
    (net (code "110") (name "unconnected-(U3-RTS-Pad24)") (class "Default")
      (node (ref "U3") (pin "24") (pinfunction "RTS_24") (pintype "output+no_connect"))
    )
    (net (code "111") (name "unconnected-(U3-SUSPEND-Pad12)") (class "Default")
      (node (ref "U3") (pin "12") (pinfunction "SUSPEND_12") (pintype "output+no_connect"))
    )
    (net (code "112") (name "unconnected-(U4-DM2+-Pad6)") (class "Default")
      (node (ref "U4") (pin "6") (pinfunction "DM2+_6") (pintype "passive"))
    )
    (net (code "113") (name "unconnected-(U4-DM2--Pad5)") (class "Default")
      (node (ref "U4") (pin "5") (pinfunction "DM2-_5") (pintype "passive"))
    )
    (net (code "114") (name "unconnected-(U4-DM4+-Pad2)") (class "Default")
      (node (ref "U4") (pin "2") (pinfunction "DM4+_2") (pintype "passive"))
    )
    (net (code "115") (name "unconnected-(U4-DM4--Pad1)") (class "Default")
      (node (ref "U4") (pin "1") (pinfunction "DM4-_1") (pintype "passive"))
    )
    (net (code "116") (name "unconnected-(U4-VD33F-Pad13)") (class "Default")
      (node (ref "U4") (pin "13") (pinfunction "VD33F_13") (pintype "passive+no_connect"))
    )
  )
)
